# echo-hello-world-plus-0p3.net
KiCad netlist of a schematic drawn in EAGLE
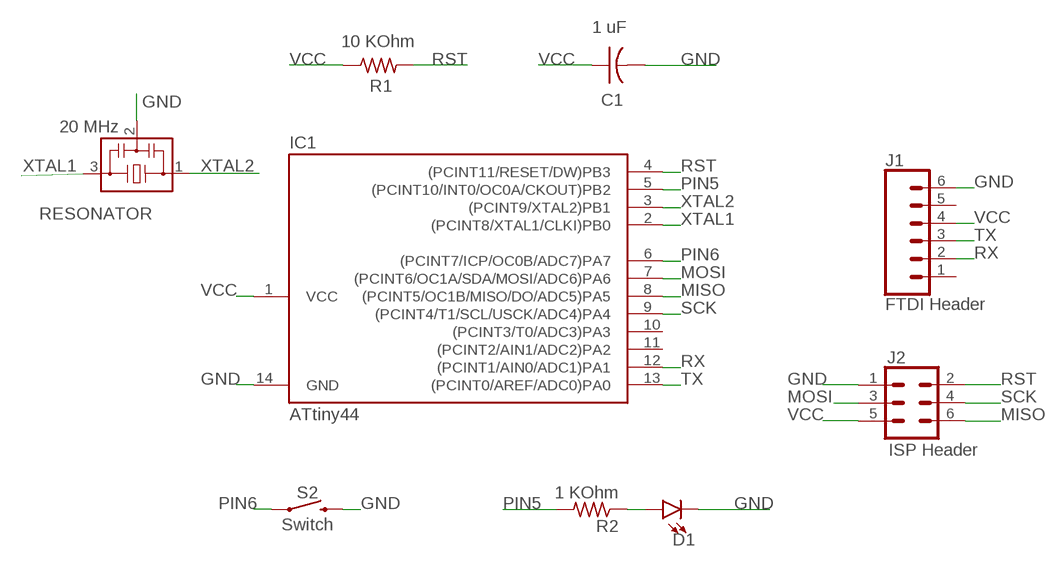
[diagram p0: schematic, sheet 1]

(export (version "E")
  (design (tool "Eeschema 10.0.6"))
  (components
    (comp (ref "C1")
      (value "1 uF")
      (footprint "eagle-import:C1206")
      (libsource (lib "eagle-import") (part "C-USC1206"))
    )
    (comp (ref "D1")
      (value "LED1206")
      (footprint "eagle-import:LED-1206")
      (libsource (lib "eagle-import") (part "LED1206"))
    )
    (comp (ref "IC1")
      (value "ATtiny44")
      (footprint "eagle-import:SOIC14")
      (libsource (lib "eagle-import") (part "ATTINY44-SSU"))
    )
    (comp (ref "J1")
      (value "FTDI Header")
      (footprint "eagle-import:1X06_SMD_MALE")
      (libsource (lib "eagle-import") (part "CONN_06SMD_MALE"))
    )
    (comp (ref "J2")
      (value "ISP Header")
      (footprint "eagle-import:2X3_SMD")
      (libsource (lib "eagle-import") (part "CONN_03X2FEMALE_SMD"))
    )
    (comp (ref "R1")
      (value "10 KOhm")
      (footprint "eagle-import:R1206")
      (libsource (lib "eagle-import") (part "R-US_R1206"))
    )
    (comp (ref "R2")
      (value "1 KOhm")
      (footprint "eagle-import:M1206")
      (libsource (lib "eagle-import") (part "resistor_348_R-US_M1206"))
    )
    (comp (ref "RESONATOR")
      (value "20 MHz")
      (footprint "eagle-import:EFOBM")
      (libsource (lib "eagle-import") (part "RESONATOR"))
    )
    (comp (ref "S2")
      (value "Switch")
      (footprint "eagle-import:TACTILE_SWITCH_SMD_6.2MM_TALL")
      (libsource (lib "eagle-import") (part "MOMENTARY-SWITCH-SPST-SMD-6.2MM-TALL"))
    )
  )
  (nets
    (net (code "1") (name "/GND") (class "Default")
      (node (ref "C1") (pin "2") (pinfunction "2_2") (pintype "passive"))
      (node (ref "D1") (pin "C") (pinfunction "C_C") (pintype "passive"))
      (node (ref "IC1") (pin "14") (pinfunction "GND_14") (pintype "power_in"))
      (node (ref "J1") (pin "6") (pinfunction "6_6") (pintype "passive"))
      (node (ref "J2") (pin "1") (pinfunction "1_1") (pintype "bidirectional"))
      (node (ref "RESONATOR") (pin "2") (pinfunction "2_2") (pintype "passive"))
      (node (ref "S2") (pin "B2") (pinfunction "2_B2") (pintype "passive"))
    )
    (net (code "2") (name "/MISO") (class "Default")
      (node (ref "IC1") (pin "8") (pinfunction "(PCINT5/OC1B/MISO/DO/ADC5)PA5_8") (pintype "bidirectional"))
      (node (ref "J2") (pin "6") (pinfunction "6_6") (pintype "bidirectional"))
    )
    (net (code "3") (name "/MOSI") (class "Default")
      (node (ref "IC1") (pin "7") (pinfunction "(PCINT6/OC1A/SDA/MOSI/ADC6)PA6_7") (pintype "bidirectional"))
      (node (ref "J2") (pin "3") (pinfunction "3_3") (pintype "bidirectional"))
    )
    (net (code "4") (name "/PIN5") (class "Default")
      (node (ref "IC1") (pin "5") (pinfunction "(PCINT10/INT0/OC0A/CKOUT)PB2_5") (pintype "bidirectional"))
      (node (ref "R2") (pin "2") (pinfunction "2_2") (pintype "passive"))
    )
    (net (code "5") (name "/PIN6") (class "Default")
      (node (ref "IC1") (pin "6") (pinfunction "(PCINT7/ICP/OC0B/ADC7)PA7_6") (pintype "bidirectional"))
      (node (ref "S2") (pin "A2") (pinfunction "1_A2") (pintype "passive"))
    )
    (net (code "6") (name "/RST") (class "Default")
      (node (ref "IC1") (pin "4") (pinfunction "(PCINT11/RESET/DW)PB3_4") (pintype "bidirectional"))
      (node (ref "J2") (pin "2") (pinfunction "2_2") (pintype "bidirectional"))
      (node (ref "R1") (pin "2") (pinfunction "2_2") (pintype "passive"))
    )
    (net (code "7") (name "/RX") (class "Default")
      (node (ref "IC1") (pin "12") (pinfunction "(PCINT1/AIN0/ADC1)PA1_12") (pintype "bidirectional"))
      (node (ref "J1") (pin "2") (pinfunction "2_2") (pintype "passive"))
    )
    (net (code "8") (name "/SCK") (class "Default")
      (node (ref "IC1") (pin "9") (pinfunction "(PCINT4/T1/SCL/USCK/ADC4)PA4_9") (pintype "bidirectional"))
      (node (ref "J2") (pin "4") (pinfunction "4_4") (pintype "bidirectional"))
    )
    (net (code "9") (name "/TX") (class "Default")
      (node (ref "IC1") (pin "13") (pinfunction "(PCINT0/AREF/ADC0)PA0_13") (pintype "bidirectional"))
      (node (ref "J1") (pin "3") (pinfunction "3_3") (pintype "passive"))
    )
    (net (code "10") (name "/VCC") (class "Default")
      (node (ref "C1") (pin "1") (pinfunction "1_1") (pintype "passive"))
      (node (ref "IC1") (pin "1") (pinfunction "VCC_1") (pintype "power_in"))
      (node (ref "J1") (pin "4") (pinfunction "4_4") (pintype "passive"))
      (node (ref "J2") (pin "5") (pinfunction "5_5") (pintype "bidirectional"))
      (node (ref "R1") (pin "1") (pinfunction "1_1") (pintype "passive"))
    )
    (net (code "11") (name "/XTAL1") (class "Default")
      (node (ref "IC1") (pin "2") (pinfunction "(PCINT8/XTAL1/CLKI)PB0_2") (pintype "bidirectional"))
      (node (ref "RESONATOR") (pin "3") (pinfunction "3_3") (pintype "passive"))
    )
    (net (code "12") (name "/XTAL2") (class "Default")
      (node (ref "IC1") (pin "3") (pinfunction "(PCINT9/XTAL2)PB1_3") (pintype "bidirectional"))
      (node (ref "RESONATOR") (pin "1") (pinfunction "1_1") (pintype "passive"))
    )
    (net (code "13") (name "Net-(D1-PadA)") (class "Default")
      (node (ref "D1") (pin "A") (pinfunction "A_A") (pintype "passive"))
      (node (ref "R2") (pin "1") (pinfunction "1_1") (pintype "passive"))
    )
    (net (code "14") (name "unconnected-(IC1-(PCINT2{slash}AIN1{slash}ADC2)PA2-Pad11)") (class "Default")
      (node (ref "IC1") (pin "11") (pinfunction "(PCINT2/AIN1/ADC2)PA2_11") (pintype "bidirectional"))
    )
    (net (code "15") (name "unconnected-(IC1-(PCINT3{slash}T0{slash}ADC3)PA3-Pad10)") (class "Default")
      (node (ref "IC1") (pin "10") (pinfunction "(PCINT3/T0/ADC3)PA3_10") (pintype "bidirectional"))
    )
    (net (code "16") (name "unconnected-(J1-Pad1)") (class "Default")
      (node (ref "J1") (pin "1") (pinfunction "1_1") (pintype "passive"))
    )
    (net (code "17") (name "unconnected-(J1-Pad5)") (class "Default")
      (node (ref "J1") (pin "5") (pinfunction "5_5") (pintype "passive"))
    )
  )
)
